# EXTERNAL-INTERFACES.net
KiCad netlist of a schematic drawn in Altium Designer
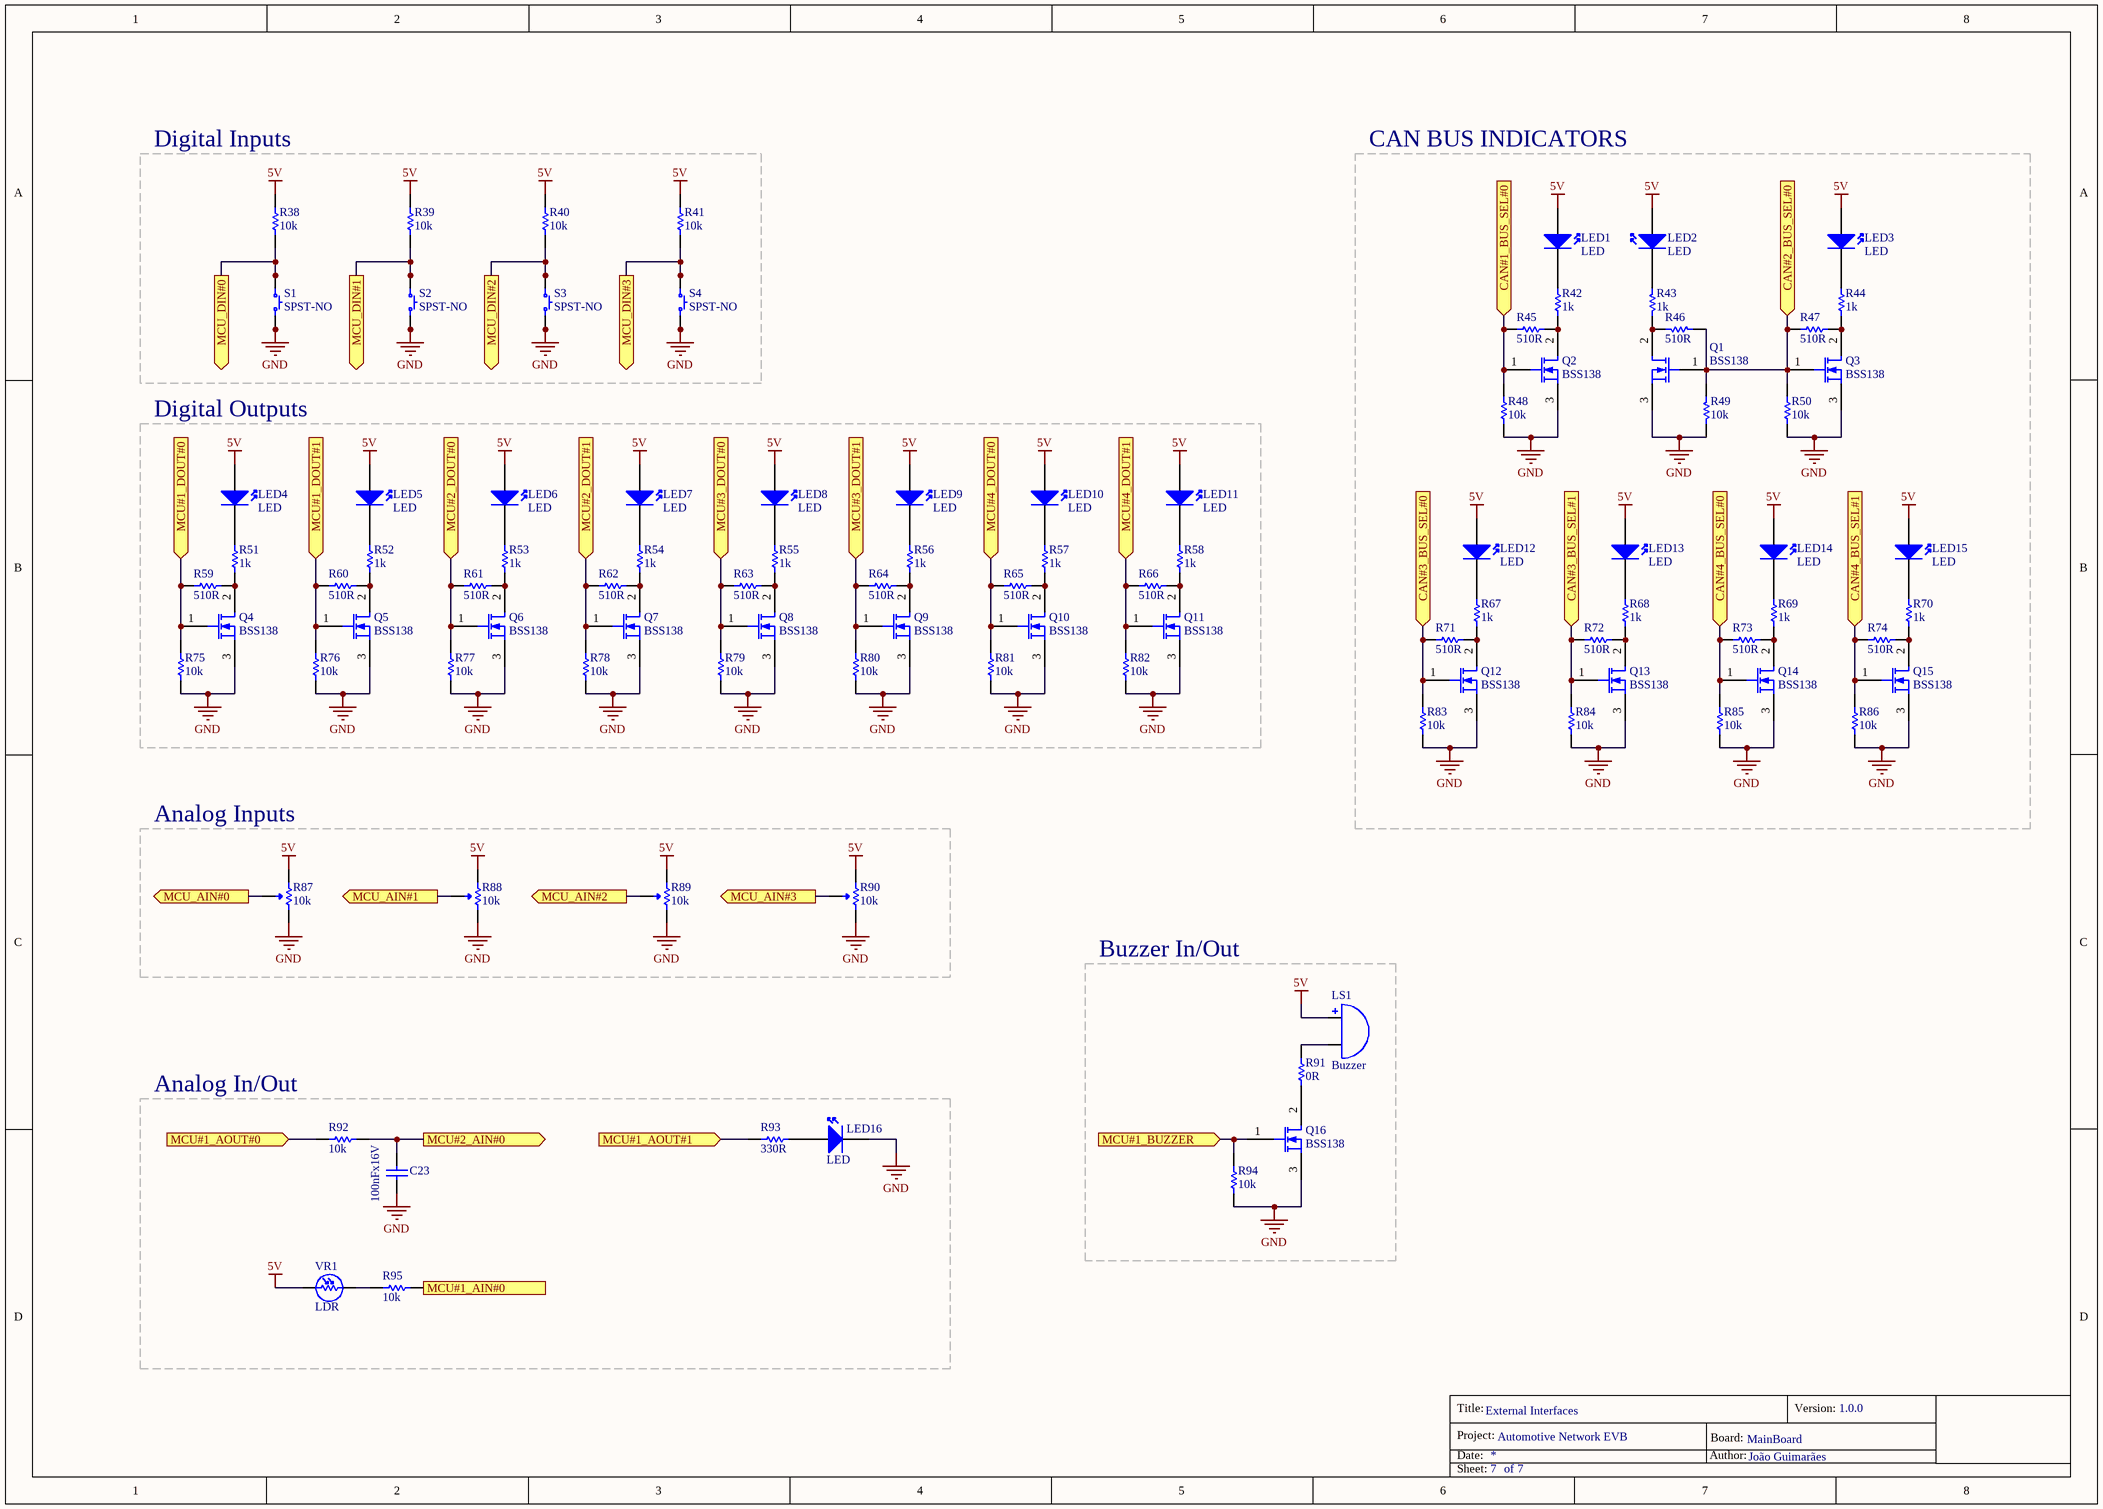
[diagram p0: EXTERNAL-INTERFACES.SchDoc]

(export (version "E")
  (design (tool "Eeschema 10.0.6"))
  (components
    (comp (ref "C23")
      (value "100nFx16V")
      (footprint "DISC-0603")
      (description "Capacitor")
      (libsource (lib "IntLib") (part "Cap"))
    )
    (comp (ref "LED1") (value "LED") (footprint "DISC-LED-1206") (libsource (lib "IntLib") (part "LED")))
    (comp (ref "LED2") (value "LED") (footprint "DISC-LED-1206") (libsource (lib "IntLib") (part "LED")))
    (comp (ref "LED3") (value "LED") (footprint "DISC-LED-1206") (libsource (lib "IntLib") (part "LED")))
    (comp (ref "LED4") (value "LED") (footprint "DISC-LED-0.1-PTH") (libsource (lib "IntLib") (part "LED")))
    (comp (ref "LED5") (value "LED") (footprint "DISC-LED-0.1-PTH") (libsource (lib "IntLib") (part "LED")))
    (comp (ref "LED6") (value "LED") (footprint "DISC-LED-0.1-PTH") (libsource (lib "IntLib") (part "LED")))
    (comp (ref "LED7") (value "LED") (footprint "DISC-LED-0.1-PTH") (libsource (lib "IntLib") (part "LED")))
    (comp (ref "LED8") (value "LED") (footprint "DISC-LED-0.1-PTH") (libsource (lib "IntLib") (part "LED")))
    (comp (ref "LED9") (value "LED") (footprint "DISC-LED-0.1-PTH") (libsource (lib "IntLib") (part "LED")))
    (comp (ref "LED10") (value "LED") (footprint "DISC-LED-0.1-PTH") (libsource (lib "IntLib") (part "LED")))
    (comp (ref "LED11") (value "LED") (footprint "DISC-LED-0.1-PTH") (libsource (lib "IntLib") (part "LED")))
    (comp (ref "LED12") (value "LED") (footprint "DISC-LED-1206") (libsource (lib "IntLib") (part "LED")))
    (comp (ref "LED13") (value "LED") (footprint "DISC-LED-1206") (libsource (lib "IntLib") (part "LED")))
    (comp (ref "LED14") (value "LED") (footprint "DISC-LED-1206") (libsource (lib "IntLib") (part "LED")))
    (comp (ref "LED15") (value "LED") (footprint "DISC-LED-1206") (libsource (lib "IntLib") (part "LED")))
    (comp (ref "LED16") (value "LED") (footprint "DISC-LED-0.1-PTH") (libsource (lib "IntLib") (part "LED")))
    (comp (ref "LS1")
      (value "Buzzer")
      (footprint "DISC-BUZZER-0.3-PTH")
      (libsource (lib "IntLib") (part "Buzzer"))
    )
    (comp (ref "Q1")
      (value "BSS138")
      (footprint "DISC-SOT-23")
      (description "Transistor NMOS")
      (libsource (lib "IntLib") (part "Transistor-NMOS(GDS)"))
    )
    (comp (ref "Q2")
      (value "BSS138")
      (footprint "DISC-SOT-23")
      (description "Transistor NMOS")
      (libsource (lib "IntLib") (part "Transistor-NMOS(GDS)"))
    )
    (comp (ref "Q3")
      (value "BSS138")
      (footprint "DISC-SOT-23")
      (description "Transistor NMOS")
      (libsource (lib "IntLib") (part "Transistor-NMOS(GDS)"))
    )
    (comp (ref "Q4")
      (value "BSS138")
      (footprint "DISC-SOT-23")
      (description "Transistor NMOS")
      (libsource (lib "IntLib") (part "Transistor-NMOS(GDS)"))
    )
    (comp (ref "Q5")
      (value "BSS138")
      (footprint "DISC-SOT-23")
      (description "Transistor NMOS")
      (libsource (lib "IntLib") (part "Transistor-NMOS(GDS)"))
    )
    (comp (ref "Q6")
      (value "BSS138")
      (footprint "DISC-SOT-23")
      (description "Transistor NMOS")
      (libsource (lib "IntLib") (part "Transistor-NMOS(GDS)"))
    )
    (comp (ref "Q7")
      (value "BSS138")
      (footprint "DISC-SOT-23")
      (description "Transistor NMOS")
      (libsource (lib "IntLib") (part "Transistor-NMOS(GDS)"))
    )
    (comp (ref "Q8")
      (value "BSS138")
      (footprint "DISC-SOT-23")
      (description "Transistor NMOS")
      (libsource (lib "IntLib") (part "Transistor-NMOS(GDS)"))
    )
    (comp (ref "Q9")
      (value "BSS138")
      (footprint "DISC-SOT-23")
      (description "Transistor NMOS")
      (libsource (lib "IntLib") (part "Transistor-NMOS(GDS)"))
    )
    (comp (ref "Q10")
      (value "BSS138")
      (footprint "DISC-SOT-23")
      (description "Transistor NMOS")
      (libsource (lib "IntLib") (part "Transistor-NMOS(GDS)"))
    )
    (comp (ref "Q11")
      (value "BSS138")
      (footprint "DISC-SOT-23")
      (description "Transistor NMOS")
      (libsource (lib "IntLib") (part "Transistor-NMOS(GDS)"))
    )
    (comp (ref "Q12")
      (value "BSS138")
      (footprint "DISC-SOT-23")
      (description "Transistor NMOS")
      (libsource (lib "IntLib") (part "Transistor-NMOS(GDS)"))
    )
    (comp (ref "Q13")
      (value "BSS138")
      (footprint "DISC-SOT-23")
      (description "Transistor NMOS")
      (libsource (lib "IntLib") (part "Transistor-NMOS(GDS)"))
    )
    (comp (ref "Q14")
      (value "BSS138")
      (footprint "DISC-SOT-23")
      (description "Transistor NMOS")
      (libsource (lib "IntLib") (part "Transistor-NMOS(GDS)"))
    )
    (comp (ref "Q15")
      (value "BSS138")
      (footprint "DISC-SOT-23")
      (description "Transistor NMOS")
      (libsource (lib "IntLib") (part "Transistor-NMOS(GDS)"))
    )
    (comp (ref "Q16")
      (value "BSS138")
      (footprint "DISC-SOT-23")
      (description "Transistor NMOS")
      (libsource (lib "IntLib") (part "Transistor-NMOS(GDS)"))
    )
    (comp (ref "R38") (value "10k") (footprint "DISC-0603") (libsource (lib "IntLib") (part "Res")))
    (comp (ref "R39") (value "10k") (footprint "DISC-0603") (libsource (lib "IntLib") (part "Res")))
    (comp (ref "R40") (value "10k") (footprint "DISC-0603") (libsource (lib "IntLib") (part "Res")))
    (comp (ref "R41") (value "10k") (footprint "DISC-0603") (libsource (lib "IntLib") (part "Res")))
    (comp (ref "R42") (value "1k") (footprint "DISC-0603") (libsource (lib "IntLib") (part "Res")))
    (comp (ref "R43") (value "1k") (footprint "DISC-0603") (libsource (lib "IntLib") (part "Res")))
    (comp (ref "R44") (value "1k") (footprint "DISC-0603") (libsource (lib "IntLib") (part "Res")))
    (comp (ref "R45") (value "510R") (footprint "DISC-0603") (libsource (lib "IntLib") (part "Res")))
    (comp (ref "R46") (value "510R") (footprint "DISC-0603") (libsource (lib "IntLib") (part "Res")))
    (comp (ref "R47") (value "510R") (footprint "DISC-0603") (libsource (lib "IntLib") (part "Res")))
    (comp (ref "R48") (value "10k") (footprint "DISC-0603") (libsource (lib "IntLib") (part "Res")))
    (comp (ref "R49") (value "10k") (footprint "DISC-0603") (libsource (lib "IntLib") (part "Res")))
    (comp (ref "R50") (value "10k") (footprint "DISC-0603") (libsource (lib "IntLib") (part "Res")))
    (comp (ref "R51") (value "1k") (footprint "DISC-0603") (libsource (lib "IntLib") (part "Res")))
    (comp (ref "R52") (value "1k") (footprint "DISC-0603") (libsource (lib "IntLib") (part "Res")))
    (comp (ref "R53") (value "1k") (footprint "DISC-0603") (libsource (lib "IntLib") (part "Res")))
    (comp (ref "R54") (value "1k") (footprint "DISC-0603") (libsource (lib "IntLib") (part "Res")))
    (comp (ref "R55") (value "1k") (footprint "DISC-0603") (libsource (lib "IntLib") (part "Res")))
    (comp (ref "R56") (value "1k") (footprint "DISC-0603") (libsource (lib "IntLib") (part "Res")))
    (comp (ref "R57") (value "1k") (footprint "DISC-0603") (libsource (lib "IntLib") (part "Res")))
    (comp (ref "R58") (value "1k") (footprint "DISC-0603") (libsource (lib "IntLib") (part "Res")))
    (comp (ref "R59") (value "510R") (footprint "DISC-0603") (libsource (lib "IntLib") (part "Res")))
    (comp (ref "R60") (value "510R") (footprint "DISC-0603") (libsource (lib "IntLib") (part "Res")))
    (comp (ref "R61") (value "510R") (footprint "DISC-0603") (libsource (lib "IntLib") (part "Res")))
    (comp (ref "R62") (value "510R") (footprint "DISC-0603") (libsource (lib "IntLib") (part "Res")))
    (comp (ref "R63") (value "510R") (footprint "DISC-0603") (libsource (lib "IntLib") (part "Res")))
    (comp (ref "R64") (value "510R") (footprint "DISC-0603") (libsource (lib "IntLib") (part "Res")))
    (comp (ref "R65") (value "510R") (footprint "DISC-0603") (libsource (lib "IntLib") (part "Res")))
    (comp (ref "R66") (value "510R") (footprint "DISC-0603") (libsource (lib "IntLib") (part "Res")))
    (comp (ref "R67") (value "1k") (footprint "DISC-0603") (libsource (lib "IntLib") (part "Res")))
    (comp (ref "R68") (value "1k") (footprint "DISC-0603") (libsource (lib "IntLib") (part "Res")))
    (comp (ref "R69") (value "1k") (footprint "DISC-0603") (libsource (lib "IntLib") (part "Res")))
    (comp (ref "R70") (value "1k") (footprint "DISC-0603") (libsource (lib "IntLib") (part "Res")))
    (comp (ref "R71") (value "510R") (footprint "DISC-0603") (libsource (lib "IntLib") (part "Res")))
    (comp (ref "R72") (value "510R") (footprint "DISC-0603") (libsource (lib "IntLib") (part "Res")))
    (comp (ref "R73") (value "510R") (footprint "DISC-0603") (libsource (lib "IntLib") (part "Res")))
    (comp (ref "R74") (value "510R") (footprint "DISC-0603") (libsource (lib "IntLib") (part "Res")))
    (comp (ref "R75") (value "10k") (footprint "DISC-0603") (libsource (lib "IntLib") (part "Res")))
    (comp (ref "R76") (value "10k") (footprint "DISC-0603") (libsource (lib "IntLib") (part "Res")))
    (comp (ref "R77") (value "10k") (footprint "DISC-0603") (libsource (lib "IntLib") (part "Res")))
    (comp (ref "R78") (value "10k") (footprint "DISC-0603") (libsource (lib "IntLib") (part "Res")))
    (comp (ref "R79") (value "10k") (footprint "DISC-0603") (libsource (lib "IntLib") (part "Res")))
    (comp (ref "R80") (value "10k") (footprint "DISC-0603") (libsource (lib "IntLib") (part "Res")))
    (comp (ref "R81") (value "10k") (footprint "DISC-0603") (libsource (lib "IntLib") (part "Res")))
    (comp (ref "R82") (value "10k") (footprint "DISC-0603") (libsource (lib "IntLib") (part "Res")))
    (comp (ref "R83") (value "10k") (footprint "DISC-0603") (libsource (lib "IntLib") (part "Res")))
    (comp (ref "R84") (value "10k") (footprint "DISC-0603") (libsource (lib "IntLib") (part "Res")))
    (comp (ref "R85") (value "10k") (footprint "DISC-0603") (libsource (lib "IntLib") (part "Res")))
    (comp (ref "R86") (value "10k") (footprint "DISC-0603") (libsource (lib "IntLib") (part "Res")))
    (comp (ref "R87")
      (value "10k")
      (footprint "DISC-TRIMPOT-TSR-3386")
      (description "COM-09806")
      (libsource (lib "IntLib") (part "VariableResistor"))
    )
    (comp (ref "R88")
      (value "10k")
      (footprint "DISC-TRIMPOT-TSR-3386")
      (description "COM-09806")
      (libsource (lib "IntLib") (part "VariableResistor"))
    )
    (comp (ref "R89")
      (value "10k")
      (footprint "DISC-TRIMPOT-TSR-3386")
      (description "COM-09806")
      (libsource (lib "IntLib") (part "VariableResistor"))
    )
    (comp (ref "R90")
      (value "10k")
      (footprint "DISC-TRIMPOT-TSR-3386")
      (description "COM-09806")
      (libsource (lib "IntLib") (part "VariableResistor"))
    )
    (comp (ref "R91") (value "0R") (footprint "DISC-0603") (libsource (lib "IntLib") (part "Res")))
    (comp (ref "R92")
      (value "10k")
      (footprint "DISC-0603")
      (description "Resistor")
      (libsource (lib "IntLib") (part "Res"))
    )
    (comp (ref "R93") (value "330R") (footprint "DISC-0603") (libsource (lib "IntLib") (part "Res")))
    (comp (ref "R94") (value "10k") (footprint "DISC-0603") (libsource (lib "IntLib") (part "Res")))
    (comp (ref "R95")
      (value "10k")
      (footprint "DISC-0603")
      (description "Resistor")
      (libsource (lib "IntLib") (part "Res"))
    )
    (comp (ref "S1")
      (value "SPST-NO")
      (footprint "DISC-PUSHBUTTON-4P-PTH")
      (libsource (lib "IntLib") (part "SPST-NO"))
    )
    (comp (ref "S2")
      (value "SPST-NO")
      (footprint "DISC-PUSHBUTTON-4P-PTH")
      (libsource (lib "IntLib") (part "SPST-NO"))
    )
    (comp (ref "S3")
      (value "SPST-NO")
      (footprint "DISC-PUSHBUTTON-4P-PTH")
      (libsource (lib "IntLib") (part "SPST-NO"))
    )
    (comp (ref "S4")
      (value "SPST-NO")
      (footprint "DISC-PUSHBUTTON-4P-PTH")
      (libsource (lib "IntLib") (part "SPST-NO"))
    )
    (comp (ref "VR1")
      (value "LDR")
      (footprint "DISC-LDR")
      (description "Resistor")
      (libsource (lib "IntLib") (part "LDR"))
    )
  )
  (nets
    (net (code "1") (name "/CAN#1_BUS_SEL#0") (class "Default")
      (node (ref "Q2") (pin "1") (pinfunction "g_1") (pintype "passive"))
      (node (ref "R45") (pin "2") (pinfunction "2_2") (pintype "passive"))
      (node (ref "R48") (pin "2") (pinfunction "2_2") (pintype "passive"))
    )
    (net (code "2") (name "/CAN#2_BUS_SEL#0") (class "Default")
      (node (ref "Q1") (pin "1") (pinfunction "g_1") (pintype "passive"))
      (node (ref "Q3") (pin "1") (pinfunction "g_1") (pintype "passive"))
      (node (ref "R46") (pin "2") (pinfunction "2_2") (pintype "passive"))
      (node (ref "R47") (pin "2") (pinfunction "2_2") (pintype "passive"))
      (node (ref "R49") (pin "2") (pinfunction "2_2") (pintype "passive"))
      (node (ref "R50") (pin "2") (pinfunction "2_2") (pintype "passive"))
    )
    (net (code "3") (name "/CAN#3_BUS_SEL#0") (class "Default")
      (node (ref "Q12") (pin "1") (pinfunction "g_1") (pintype "passive"))
      (node (ref "R71") (pin "2") (pinfunction "2_2") (pintype "passive"))
      (node (ref "R83") (pin "2") (pinfunction "2_2") (pintype "passive"))
    )
    (net (code "4") (name "/CAN#3_BUS_SEL#1") (class "Default")
      (node (ref "Q13") (pin "1") (pinfunction "g_1") (pintype "passive"))
      (node (ref "R72") (pin "2") (pinfunction "2_2") (pintype "passive"))
      (node (ref "R84") (pin "2") (pinfunction "2_2") (pintype "passive"))
    )
    (net (code "5") (name "/CAN#4_BUS_SEL#0") (class "Default")
      (node (ref "Q14") (pin "1") (pinfunction "g_1") (pintype "passive"))
      (node (ref "R73") (pin "2") (pinfunction "2_2") (pintype "passive"))
      (node (ref "R85") (pin "2") (pinfunction "2_2") (pintype "passive"))
    )
    (net (code "6") (name "/CAN#4_BUS_SEL#1") (class "Default")
      (node (ref "Q15") (pin "1") (pinfunction "g_1") (pintype "passive"))
      (node (ref "R74") (pin "2") (pinfunction "2_2") (pintype "passive"))
      (node (ref "R86") (pin "2") (pinfunction "2_2") (pintype "passive"))
    )
    (net (code "7") (name "/MCU#1_AIN#0") (class "Default")
      (node (ref "R95") (pin "2") (pinfunction "2_2") (pintype "passive"))
    )
    (net (code "8") (name "/MCU#1_AOUT#0") (class "Default")
      (node (ref "R92") (pin "1") (pinfunction "1_1") (pintype "passive"))
    )
    (net (code "9") (name "/MCU#1_AOUT#1") (class "Default")
      (node (ref "R93") (pin "2") (pinfunction "2_2") (pintype "passive"))
    )
    (net (code "10") (name "/MCU#1_BUZZER") (class "Default")
      (node (ref "Q16") (pin "1") (pinfunction "g_1") (pintype "passive"))
      (node (ref "R94") (pin "2") (pinfunction "2_2") (pintype "passive"))
    )
    (net (code "11") (name "/MCU#1_DOUT#0") (class "Default")
      (node (ref "Q4") (pin "1") (pinfunction "g_1") (pintype "passive"))
      (node (ref "R59") (pin "2") (pinfunction "2_2") (pintype "passive"))
      (node (ref "R75") (pin "2") (pinfunction "2_2") (pintype "passive"))
    )
    (net (code "12") (name "/MCU#1_DOUT#1") (class "Default")
      (node (ref "Q5") (pin "1") (pinfunction "g_1") (pintype "passive"))
      (node (ref "R60") (pin "2") (pinfunction "2_2") (pintype "passive"))
      (node (ref "R76") (pin "2") (pinfunction "2_2") (pintype "passive"))
    )
    (net (code "13") (name "/MCU#2_AIN#0") (class "Default")
      (node (ref "C23") (pin "1") (pinfunction "1_1") (pintype "passive"))
      (node (ref "R92") (pin "2") (pinfunction "2_2") (pintype "passive"))
    )
    (net (code "14") (name "/MCU#2_DOUT#0") (class "Default")
      (node (ref "Q6") (pin "1") (pinfunction "g_1") (pintype "passive"))
      (node (ref "R61") (pin "2") (pinfunction "2_2") (pintype "passive"))
      (node (ref "R77") (pin "2") (pinfunction "2_2") (pintype "passive"))
    )
    (net (code "15") (name "/MCU#2_DOUT#1") (class "Default")
      (node (ref "Q7") (pin "1") (pinfunction "g_1") (pintype "passive"))
      (node (ref "R62") (pin "2") (pinfunction "2_2") (pintype "passive"))
      (node (ref "R78") (pin "2") (pinfunction "2_2") (pintype "passive"))
    )
    (net (code "16") (name "/MCU#3_DOUT#0") (class "Default")
      (node (ref "Q8") (pin "1") (pinfunction "g_1") (pintype "passive"))
      (node (ref "R63") (pin "2") (pinfunction "2_2") (pintype "passive"))
      (node (ref "R79") (pin "2") (pinfunction "2_2") (pintype "passive"))
    )
    (net (code "17") (name "/MCU#3_DOUT#1") (class "Default")
      (node (ref "Q9") (pin "1") (pinfunction "g_1") (pintype "passive"))
      (node (ref "R64") (pin "2") (pinfunction "2_2") (pintype "passive"))
      (node (ref "R80") (pin "2") (pinfunction "2_2") (pintype "passive"))
    )
    (net (code "18") (name "/MCU#4_DOUT#0") (class "Default")
      (node (ref "Q10") (pin "1") (pinfunction "g_1") (pintype "passive"))
      (node (ref "R65") (pin "2") (pinfunction "2_2") (pintype "passive"))
      (node (ref "R81") (pin "2") (pinfunction "2_2") (pintype "passive"))
    )
    (net (code "19") (name "/MCU#4_DOUT#1") (class "Default")
      (node (ref "Q11") (pin "1") (pinfunction "g_1") (pintype "passive"))
      (node (ref "R66") (pin "2") (pinfunction "2_2") (pintype "passive"))
      (node (ref "R82") (pin "2") (pinfunction "2_2") (pintype "passive"))
    )
    (net (code "20") (name "/MCU_AIN#0") (class "Default")
      (node (ref "R87") (pin "2") (pinfunction "2_2") (pintype "passive"))
    )
    (net (code "21") (name "/MCU_AIN#1") (class "Default")
      (node (ref "R88") (pin "2") (pinfunction "2_2") (pintype "passive"))
    )
    (net (code "22") (name "/MCU_AIN#2") (class "Default")
      (node (ref "R89") (pin "2") (pinfunction "2_2") (pintype "passive"))
    )
    (net (code "23") (name "/MCU_AIN#3") (class "Default")
      (node (ref "R90") (pin "2") (pinfunction "2_2") (pintype "passive"))
    )
    (net (code "24") (name "/MCU_DIN#0") (class "Default")
      (node (ref "R38") (pin "1") (pinfunction "1_1") (pintype "passive"))
      (node (ref "S1") (pin "1") (pinfunction "1_1") (pintype "passive"))
      (node (ref "S1") (pin "2") (pinfunction "2_2") (pintype "passive"))
    )
    (net (code "25") (name "/MCU_DIN#1") (class "Default")
      (node (ref "R39") (pin "1") (pinfunction "1_1") (pintype "passive"))
      (node (ref "S2") (pin "1") (pinfunction "1_1") (pintype "passive"))
      (node (ref "S2") (pin "2") (pinfunction "2_2") (pintype "passive"))
    )
    (net (code "26") (name "/MCU_DIN#2") (class "Default")
      (node (ref "R40") (pin "1") (pinfunction "1_1") (pintype "passive"))
      (node (ref "S3") (pin "1") (pinfunction "1_1") (pintype "passive"))
      (node (ref "S3") (pin "2") (pinfunction "2_2") (pintype "passive"))
    )
    (net (code "27") (name "/MCU_DIN#3") (class "Default")
      (node (ref "R41") (pin "1") (pinfunction "1_1") (pintype "passive"))
      (node (ref "S4") (pin "1") (pinfunction "1_1") (pintype "passive"))
      (node (ref "S4") (pin "2") (pinfunction "2_2") (pintype "passive"))
    )
    (net (code "28") (name "5V") (class "Default")
      (node (ref "LED1") (pin "1") (pinfunction "A_1") (pintype "passive"))
      (node (ref "LED10") (pin "1") (pinfunction "A_1") (pintype "passive"))
      (node (ref "LED11") (pin "1") (pinfunction "A_1") (pintype "passive"))
      (node (ref "LED12") (pin "1") (pinfunction "A_1") (pintype "passive"))
      (node (ref "LED13") (pin "1") (pinfunction "A_1") (pintype "passive"))
      (node (ref "LED14") (pin "1") (pinfunction "A_1") (pintype "passive"))
      (node (ref "LED15") (pin "1") (pinfunction "A_1") (pintype "passive"))
      (node (ref "LED2") (pin "1") (pinfunction "A_1") (pintype "passive"))
      (node (ref "LED3") (pin "1") (pinfunction "A_1") (pintype "passive"))
      (node (ref "LED4") (pin "1") (pinfunction "A_1") (pintype "passive"))
      (node (ref "LED5") (pin "1") (pinfunction "A_1") (pintype "passive"))
      (node (ref "LED6") (pin "1") (pinfunction "A_1") (pintype "passive"))
      (node (ref "LED7") (pin "1") (pinfunction "A_1") (pintype "passive"))
      (node (ref "LED8") (pin "1") (pinfunction "A_1") (pintype "passive"))
      (node (ref "LED9") (pin "1") (pinfunction "A_1") (pintype "passive"))
      (node (ref "LS1") (pin "1") (pinfunction "1_1") (pintype "passive"))
      (node (ref "R38") (pin "2") (pinfunction "2_2") (pintype "passive"))
      (node (ref "R39") (pin "2") (pinfunction "2_2") (pintype "passive"))
      (node (ref "R40") (pin "2") (pinfunction "2_2") (pintype "passive"))
      (node (ref "R41") (pin "2") (pinfunction "2_2") (pintype "passive"))
      (node (ref "R87") (pin "3") (pinfunction "3_3") (pintype "passive"))
      (node (ref "R88") (pin "3") (pinfunction "3_3") (pintype "passive"))
      (node (ref "R89") (pin "3") (pinfunction "3_3") (pintype "passive"))
      (node (ref "R90") (pin "3") (pinfunction "3_3") (pintype "passive"))
      (node (ref "VR1") (pin "1") (pinfunction "1_1") (pintype "passive"))
    )
    (net (code "29") (name "GND") (class "Default")
      (node (ref "C23") (pin "2") (pinfunction "2_2") (pintype "passive"))
      (node (ref "LED16") (pin "2") (pinfunction "K_2") (pintype "passive"))
      (node (ref "Q1") (pin "3") (pinfunction "S_3") (pintype "passive"))
      (node (ref "Q10") (pin "3") (pinfunction "S_3") (pintype "passive"))
      (node (ref "Q11") (pin "3") (pinfunction "S_3") (pintype "passive"))
      (node (ref "Q12") (pin "3") (pinfunction "S_3") (pintype "passive"))
      (node (ref "Q13") (pin "3") (pinfunction "S_3") (pintype "passive"))
      (node (ref "Q14") (pin "3") (pinfunction "S_3") (pintype "passive"))
      (node (ref "Q15") (pin "3") (pinfunction "S_3") (pintype "passive"))
      (node (ref "Q16") (pin "3") (pinfunction "S_3") (pintype "passive"))
      (node (ref "Q2") (pin "3") (pinfunction "S_3") (pintype "passive"))
      (node (ref "Q3") (pin "3") (pinfunction "S_3") (pintype "passive"))
      (node (ref "Q4") (pin "3") (pinfunction "S_3") (pintype "passive"))
      (node (ref "Q5") (pin "3") (pinfunction "S_3") (pintype "passive"))
      (node (ref "Q6") (pin "3") (pinfunction "S_3") (pintype "passive"))
      (node (ref "Q7") (pin "3") (pinfunction "S_3") (pintype "passive"))
      (node (ref "Q8") (pin "3") (pinfunction "S_3") (pintype "passive"))
      (node (ref "Q9") (pin "3") (pinfunction "S_3") (pintype "passive"))
      (node (ref "R48") (pin "1") (pinfunction "1_1") (pintype "passive"))
      (node (ref "R49") (pin "1") (pinfunction "1_1") (pintype "passive"))
      (node (ref "R50") (pin "1") (pinfunction "1_1") (pintype "passive"))
      (node (ref "R75") (pin "1") (pinfunction "1_1") (pintype "passive"))
      (node (ref "R76") (pin "1") (pinfunction "1_1") (pintype "passive"))
      (node (ref "R77") (pin "1") (pinfunction "1_1") (pintype "passive"))
      (node (ref "R78") (pin "1") (pinfunction "1_1") (pintype "passive"))
      (node (ref "R79") (pin "1") (pinfunction "1_1") (pintype "passive"))
      (node (ref "R80") (pin "1") (pinfunction "1_1") (pintype "passive"))
      (node (ref "R81") (pin "1") (pinfunction "1_1") (pintype "passive"))
      (node (ref "R82") (pin "1") (pinfunction "1_1") (pintype "passive"))
      (node (ref "R83") (pin "1") (pinfunction "1_1") (pintype "passive"))
      (node (ref "R84") (pin "1") (pinfunction "1_1") (pintype "passive"))
      (node (ref "R85") (pin "1") (pinfunction "1_1") (pintype "passive"))
      (node (ref "R86") (pin "1") (pinfunction "1_1") (pintype "passive"))
      (node (ref "R87") (pin "1") (pinfunction "1_1") (pintype "passive"))
      (node (ref "R88") (pin "1") (pinfunction "1_1") (pintype "passive"))
      (node (ref "R89") (pin "1") (pinfunction "1_1") (pintype "passive"))
      (node (ref "R90") (pin "1") (pinfunction "1_1") (pintype "passive"))
      (node (ref "R94") (pin "1") (pinfunction "1_1") (pintype "passive"))
      (node (ref "S1") (pin "3") (pinfunction "3_3") (pintype "passive"))
      (node (ref "S1") (pin "4") (pinfunction "4_4") (pintype "passive"))
      (node (ref "S2") (pin "3") (pinfunction "3_3") (pintype "passive"))
      (node (ref "S2") (pin "4") (pinfunction "4_4") (pintype "passive"))
      (node (ref "S3") (pin "3") (pinfunction "3_3") (pintype "passive"))
      (node (ref "S3") (pin "4") (pinfunction "4_4") (pintype "passive"))
      (node (ref "S4") (pin "3") (pinfunction "3_3") (pintype "passive"))
      (node (ref "S4") (pin "4") (pinfunction "4_4") (pintype "passive"))
    )
    (net (code "30") (name "Net-(LED1-K)") (class "Default")
      (node (ref "LED1") (pin "2") (pinfunction "K_2") (pintype "passive"))
      (node (ref "R42") (pin "2") (pinfunction "2_2") (pintype "passive"))
    )
    (net (code "31") (name "Net-(LED2-K)") (class "Default")
      (node (ref "LED2") (pin "2") (pinfunction "K_2") (pintype "passive"))
      (node (ref "R43") (pin "2") (pinfunction "2_2") (pintype "passive"))
    )
    (net (code "32") (name "Net-(LED3-K)") (class "Default")
      (node (ref "LED3") (pin "2") (pinfunction "K_2") (pintype "passive"))
      (node (ref "R44") (pin "2") (pinfunction "2_2") (pintype "passive"))
    )
    (net (code "33") (name "Net-(LED4-K)") (class "Default")
      (node (ref "LED4") (pin "2") (pinfunction "K_2") (pintype "passive"))
      (node (ref "R51") (pin "2") (pinfunction "2_2") (pintype "passive"))
    )
    (net (code "34") (name "Net-(LED5-K)") (class "Default")
      (node (ref "LED5") (pin "2") (pinfunction "K_2") (pintype "passive"))
      (node (ref "R52") (pin "2") (pinfunction "2_2") (pintype "passive"))
    )
    (net (code "35") (name "Net-(LED6-K)") (class "Default")
      (node (ref "LED6") (pin "2") (pinfunction "K_2") (pintype "passive"))
      (node (ref "R53") (pin "2") (pinfunction "2_2") (pintype "passive"))
    )
    (net (code "36") (name "Net-(LED7-K)") (class "Default")
      (node (ref "LED7") (pin "2") (pinfunction "K_2") (pintype "passive"))
      (node (ref "R54") (pin "2") (pinfunction "2_2") (pintype "passive"))
    )
    (net (code "37") (name "Net-(LED8-K)") (class "Default")
      (node (ref "LED8") (pin "2") (pinfunction "K_2") (pintype "passive"))
      (node (ref "R55") (pin "2") (pinfunction "2_2") (pintype "passive"))
    )
    (net (code "38") (name "Net-(LED9-K)") (class "Default")
      (node (ref "LED9") (pin "2") (pinfunction "K_2") (pintype "passive"))
      (node (ref "R56") (pin "2") (pinfunction "2_2") (pintype "passive"))
    )
    (net (code "39") (name "Net-(LED10-K)") (class "Default")
      (node (ref "LED10") (pin "2") (pinfunction "K_2") (pintype "passive"))
      (node (ref "R57") (pin "2") (pinfunction "2_2") (pintype "passive"))
    )
    (net (code "40") (name "Net-(LED11-K)") (class "Default")
      (node (ref "LED11") (pin "2") (pinfunction "K_2") (pintype "passive"))
      (node (ref "R58") (pin "2") (pinfunction "2_2") (pintype "passive"))
    )
    (net (code "41") (name "Net-(LED12-K)") (class "Default")
      (node (ref "LED12") (pin "2") (pinfunction "K_2") (pintype "passive"))
      (node (ref "R67") (pin "2") (pinfunction "2_2") (pintype "passive"))
    )
    (net (code "42") (name "Net-(LED13-K)") (class "Default")
      (node (ref "LED13") (pin "2") (pinfunction "K_2") (pintype "passive"))
      (node (ref "R68") (pin "2") (pinfunction "2_2") (pintype "passive"))
    )
    (net (code "43") (name "Net-(LED14-K)") (class "Default")
      (node (ref "LED14") (pin "2") (pinfunction "K_2") (pintype "passive"))
      (node (ref "R69") (pin "2") (pinfunction "2_2") (pintype "passive"))
    )
    (net (code "44") (name "Net-(LED15-K)") (class "Default")
      (node (ref "LED15") (pin "2") (pinfunction "K_2") (pintype "passive"))
      (node (ref "R70") (pin "2") (pinfunction "2_2") (pintype "passive"))
    )
    (net (code "45") (name "Net-(LED16-A)") (class "Default")
      (node (ref "LED16") (pin "1") (pinfunction "A_1") (pintype "passive"))
      (node (ref "R93") (pin "1") (pinfunction "1_1") (pintype "passive"))
    )
    (net (code "46") (name "Net-(LS1-1-Pad2)") (class "Default")
      (node (ref "LS1") (pin "2") (pinfunction "1_2") (pintype "passive"))
      (node (ref "R91") (pin "2") (pinfunction "2_2") (pintype "passive"))
    )
    (net (code "47") (name "Net-(Q1-D)") (class "Default")
      (node (ref "Q1") (pin "2") (pinfunction "D_2") (pintype "passive"))
      (node (ref "R43") (pin "1") (pinfunction "1_1") (pintype "passive"))
      (node (ref "R46") (pin "1") (pinfunction "1_1") (pintype "passive"))
    )
    (net (code "48") (name "Net-(Q2-D)") (class "Default")
      (node (ref "Q2") (pin "2") (pinfunction "D_2") (pintype "passive"))
      (node (ref "R42") (pin "1") (pinfunction "1_1") (pintype "passive"))
      (node (ref "R45") (pin "1") (pinfunction "1_1") (pintype "passive"))
    )
    (net (code "49") (name "Net-(Q3-D)") (class "Default")
      (node (ref "Q3") (pin "2") (pinfunction "D_2") (pintype "passive"))
      (node (ref "R44") (pin "1") (pinfunction "1_1") (pintype "passive"))
      (node (ref "R47") (pin "1") (pinfunction "1_1") (pintype "passive"))
    )
    (net (code "50") (name "Net-(Q4-D)") (class "Default")
      (node (ref "Q4") (pin "2") (pinfunction "D_2") (pintype "passive"))
      (node (ref "R51") (pin "1") (pinfunction "1_1") (pintype "passive"))
      (node (ref "R59") (pin "1") (pinfunction "1_1") (pintype "passive"))
    )
    (net (code "51") (name "Net-(Q5-D)") (class "Default")
      (node (ref "Q5") (pin "2") (pinfunction "D_2") (pintype "passive"))
      (node (ref "R52") (pin "1") (pinfunction "1_1") (pintype "passive"))
      (node (ref "R60") (pin "1") (pinfunction "1_1") (pintype "passive"))
    )
    (net (code "52") (name "Net-(Q6-D)") (class "Default")
      (node (ref "Q6") (pin "2") (pinfunction "D_2") (pintype "passive"))
      (node (ref "R53") (pin "1") (pinfunction "1_1") (pintype "passive"))
      (node (ref "R61") (pin "1") (pinfunction "1_1") (pintype "passive"))
    )
    (net (code "53") (name "Net-(Q7-D)") (class "Default")
      (node (ref "Q7") (pin "2") (pinfunction "D_2") (pintype "passive"))
      (node (ref "R54") (pin "1") (pinfunction "1_1") (pintype "passive"))
      (node (ref "R62") (pin "1") (pinfunction "1_1") (pintype "passive"))
    )
    (net (code "54") (name "Net-(Q8-D)") (class "Default")
      (node (ref "Q8") (pin "2") (pinfunction "D_2") (pintype "passive"))
      (node (ref "R55") (pin "1") (pinfunction "1_1") (pintype "passive"))
      (node (ref "R63") (pin "1") (pinfunction "1_1") (pintype "passive"))
    )
    (net (code "55") (name "Net-(Q9-D)") (class "Default")
      (node (ref "Q9") (pin "2") (pinfunction "D_2") (pintype "passive"))
      (node (ref "R56") (pin "1") (pinfunction "1_1") (pintype "passive"))
      (node (ref "R64") (pin "1") (pinfunction "1_1") (pintype "passive"))
    )
    (net (code "56") (name "Net-(Q10-D)") (class "Default")
      (node (ref "Q10") (pin "2") (pinfunction "D_2") (pintype "passive"))
      (node (ref "R57") (pin "1") (pinfunction "1_1") (pintype "passive"))
      (node (ref "R65") (pin "1") (pinfunction "1_1") (pintype "passive"))
    )
    (net (code "57") (name "Net-(Q11-D)") (class "Default")
      (node (ref "Q11") (pin "2") (pinfunction "D_2") (pintype "passive"))
      (node (ref "R58") (pin "1") (pinfunction "1_1") (pintype "passive"))
      (node (ref "R66") (pin "1") (pinfunction "1_1") (pintype "passive"))
    )
    (net (code "58") (name "Net-(Q12-D)") (class "Default")
      (node (ref "Q12") (pin "2") (pinfunction "D_2") (pintype "passive"))
      (node (ref "R67") (pin "1") (pinfunction "1_1") (pintype "passive"))
      (node (ref "R71") (pin "1") (pinfunction "1_1") (pintype "passive"))
    )
    (net (code "59") (name "Net-(Q13-D)") (class "Default")
      (node (ref "Q13") (pin "2") (pinfunction "D_2") (pintype "passive"))
      (node (ref "R68") (pin "1") (pinfunction "1_1") (pintype "passive"))
      (node (ref "R72") (pin "1") (pinfunction "1_1") (pintype "passive"))
    )
    (net (code "60") (name "Net-(Q14-D)") (class "Default")
      (node (ref "Q14") (pin "2") (pinfunction "D_2") (pintype "passive"))
      (node (ref "R69") (pin "1") (pinfunction "1_1") (pintype "passive"))
      (node (ref "R73") (pin "1") (pinfunction "1_1") (pintype "passive"))
    )
    (net (code "61") (name "Net-(Q15-D)") (class "Default")
      (node (ref "Q15") (pin "2") (pinfunction "D_2") (pintype "passive"))
      (node (ref "R70") (pin "1") (pinfunction "1_1") (pintype "passive"))
      (node (ref "R74") (pin "1") (pinfunction "1_1") (pintype "passive"))
    )
    (net (code "62") (name "Net-(Q16-D)") (class "Default")
      (node (ref "Q16") (pin "2") (pinfunction "D_2") (pintype "passive"))
      (node (ref "R91") (pin "1") (pinfunction "1_1") (pintype "passive"))
    )
    (net (code "63") (name "Net-(R95-Pad1)") (class "Default")
      (node (ref "R95") (pin "1") (pinfunction "1_1") (pintype "passive"))
      (node (ref "VR1") (pin "2") (pinfunction "2_2") (pintype "passive"))
    )
  )
)
